# REV_2025.net
KiCad netlist of a schematic drawn in Altium Designer
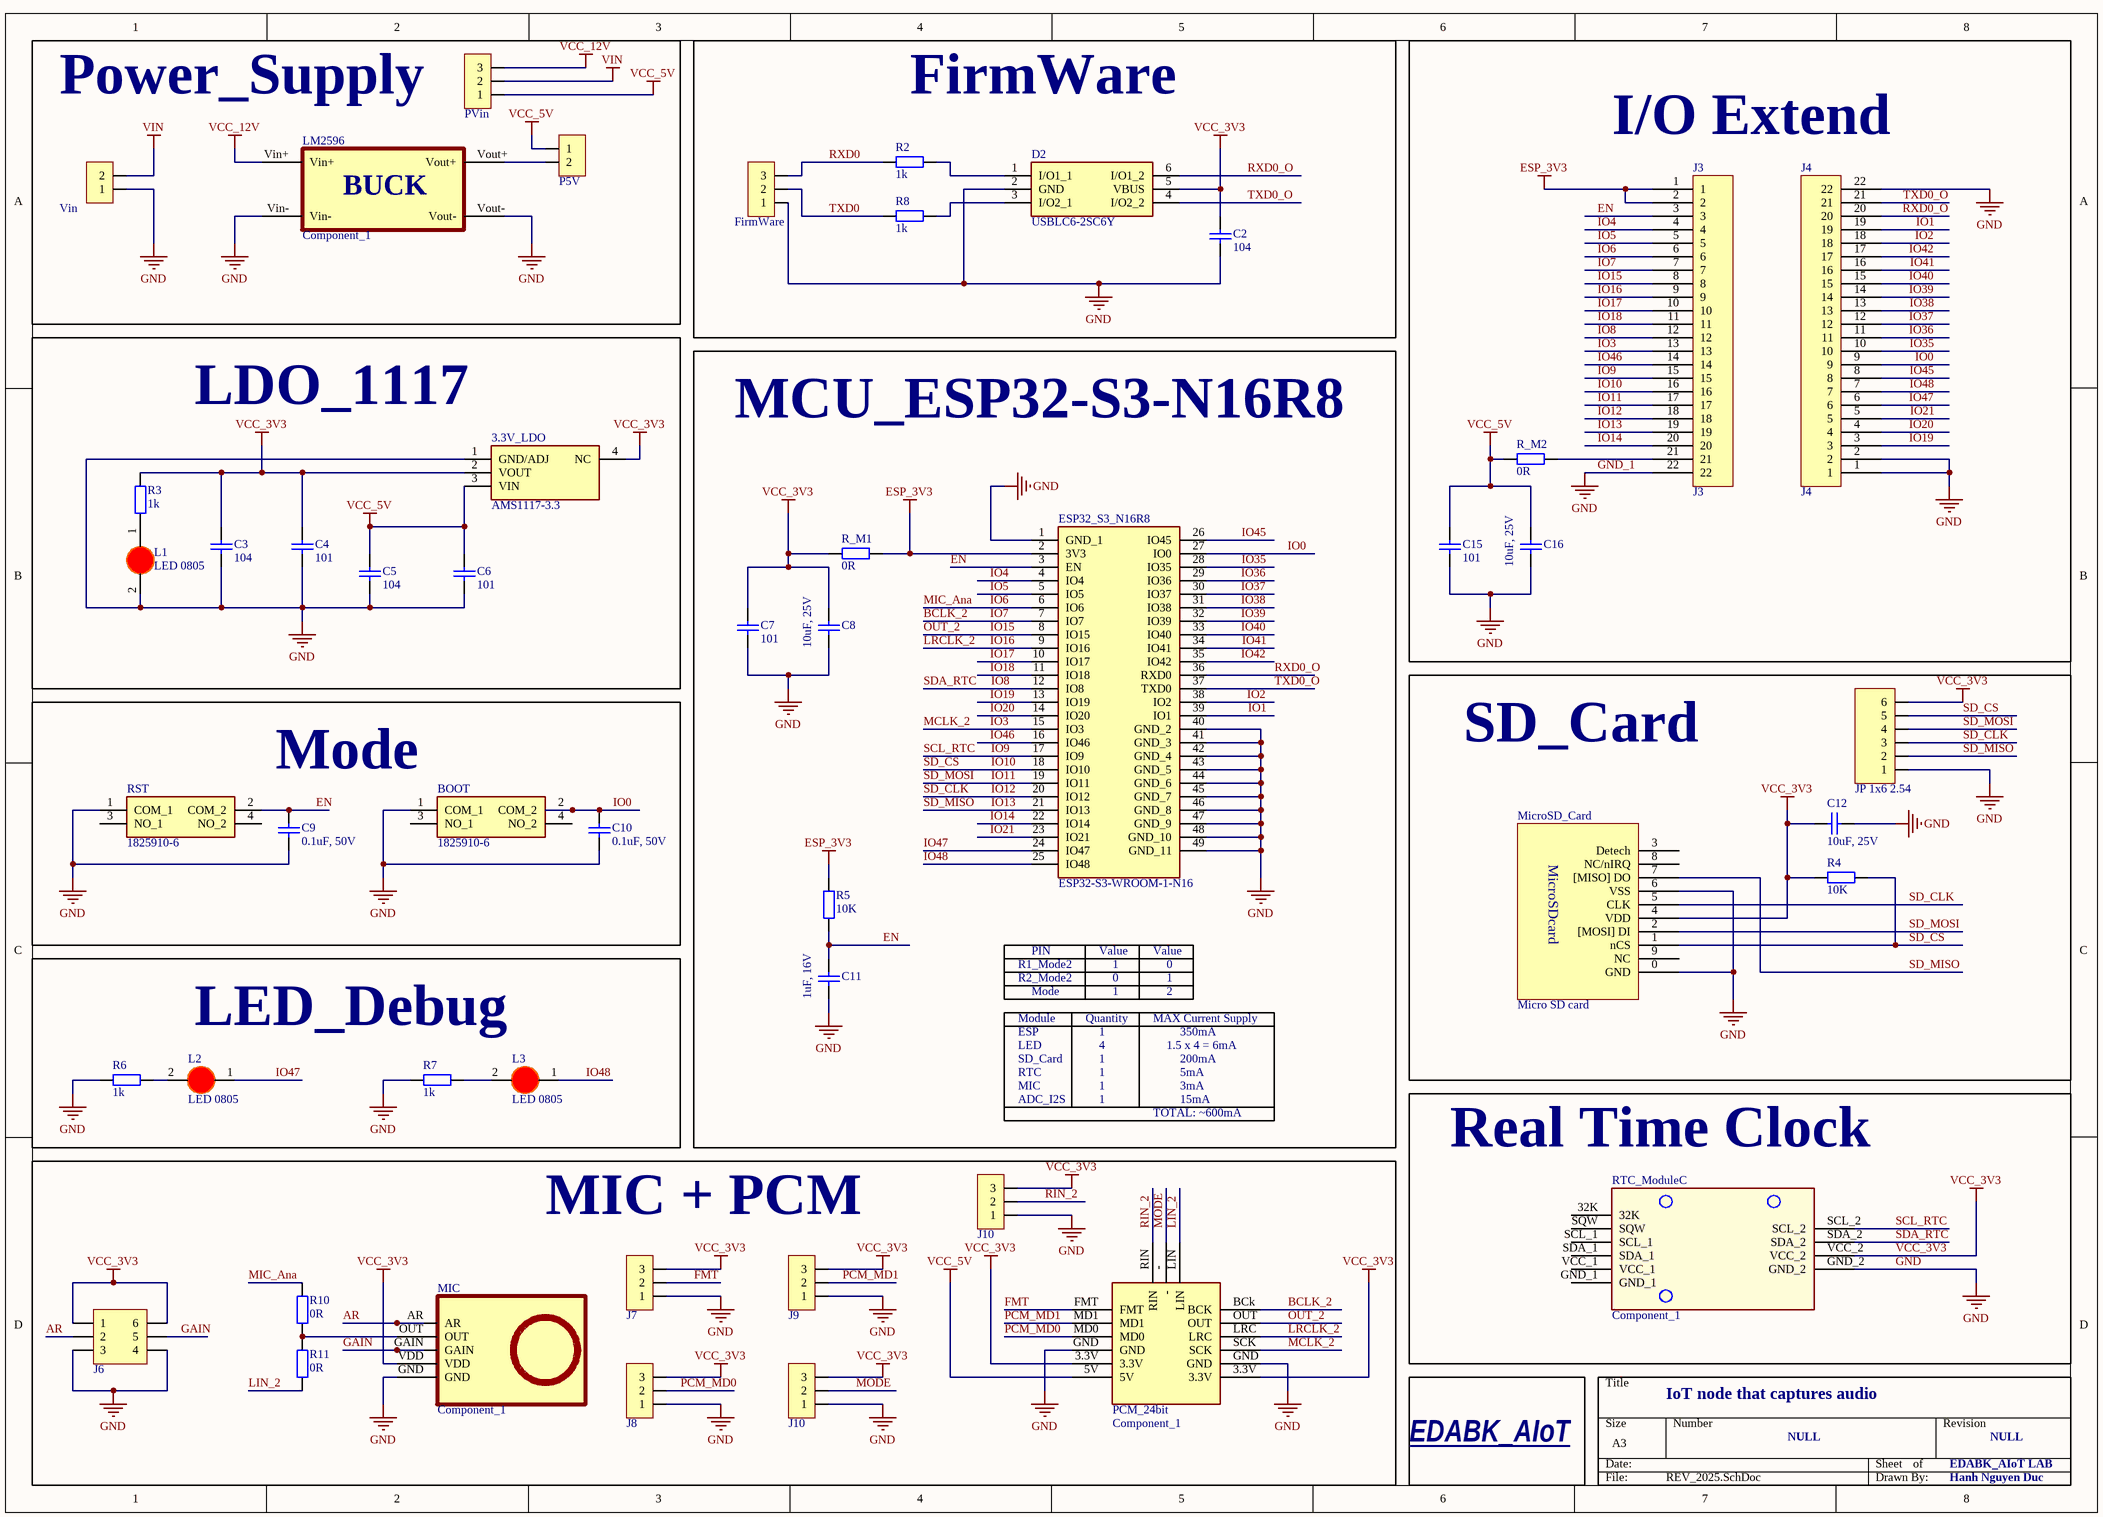
[diagram p0: REV_2025.SchDoc]

(export (version "E")
  (design (tool "Eeschema 10.0.6"))
  (components
    (comp (ref "3.3V_LDO")
      (value "AMS1117-3.3")
      (footprint "SamacSys:SOT229P700X180-4N")
      (description "Integrated Circuit")
      (libsource (lib "*") (part "AMS1117-3.3"))
    )
    (comp (ref "BOOT")
      (value "1825910-6")
      (footprint "SamacSys:18259106")
      (description "Switch")
      (fields (field (name "MOUSER PART NUMBER") "650-1825910-6"))
      (libsource (lib "*") (part "1825910-6"))
    )
    (comp (ref "C2")
      (value "104")
      (footprint "tu 0603")
      (description "Dán")
      (libsource (lib "Altium_Lib_by_KhueNguyenCreator") (part "Tu 0603 104 50V 10%"))
    )
    (comp (ref "C3")
      (value "104")
      (footprint "tu 0603")
      (description "Dán")
      (libsource (lib "Altium_Lib_by_KhueNguyenCreator") (part "Tu 0603 104 50V 10%"))
    )
    (comp (ref "C4")
      (value "101")
      (footprint "tu 0805")
      (description "Dán")
      (libsource (lib "Altium_Lib_by_KhueNguyenCreator") (part "Tu 0805 101 50V 20%"))
    )
    (comp (ref "C5")
      (value "104")
      (footprint "tu 0603")
      (description "Dán")
      (libsource (lib "Altium_Lib_by_KhueNguyenCreator") (part "Tu 0603 104 50V 10%"))
    )
    (comp (ref "C6")
      (value "101")
      (footprint "tu 0805")
      (description "Dán")
      (libsource (lib "Altium_Lib_by_KhueNguyenCreator") (part "Tu 0805 101 50V 20%"))
    )
    (comp (ref "C7")
      (value "101")
      (footprint "tu 0805")
      (description "Dán")
      (libsource (lib "Altium_Lib_by_KhueNguyenCreator") (part "Tu 0805 101 50V 20%"))
    )
    (comp (ref "C8")
      (value "10uF, 25V")
      (footprint "tu 0603")
      (description "Dán")
      (libsource (lib "Altium_Lib_by_KhueNguyenCreator") (part "Tu 0603 104 50V 10%"))
    )
    (comp (ref "C9")
      (value "0.1uF, 50V")
      (footprint "tu 0603")
      (description "Dán")
      (libsource (lib "Altium_Lib_by_KhueNguyenCreator") (part "Tu 0603 103 50V 10%"))
    )
    (comp (ref "C10")
      (value "0.1uF, 50V")
      (footprint "tu 0603")
      (description "Dán")
      (libsource (lib "Altium_Lib_by_KhueNguyenCreator") (part "Tu 0603 103 50V 10%"))
    )
    (comp (ref "C11")
      (value "1uF, 16V")
      (footprint "tu 0603")
      (description "Dán")
      (libsource (lib "Altium_Lib_by_KhueNguyenCreator") (part "Tu 0603 104 50V 10%"))
    )
    (comp (ref "C12")
      (value "10uF, 25V")
      (footprint "tu 0603")
      (description "Dán")
      (libsource (lib "Altium_Lib_by_KhueNguyenCreator") (part "Tu 0603 104 50V 10%"))
    )
    (comp (ref "C15")
      (value "101")
      (footprint "tu 0805")
      (description "Dán")
      (libsource (lib "Altium_Lib_by_KhueNguyenCreator") (part "Tu 0805 101 50V 20%"))
    )
    (comp (ref "C16")
      (value "10uF, 25V")
      (footprint "tu 0603")
      (description "Dán")
      (libsource (lib "Altium_Lib_by_KhueNguyenCreator") (part "Tu 0603 104 50V 10%"))
    )
    (comp (ref "D2")
      (value "USBLC6-2SC6Y")
      (footprint "SamacSys:SOT95P280X145-6N")
      (description "Diode")
      (fields (field (name "MOUSER PART NUMBER") "511-USBLC6-2SC6Y"))
      (libsource (lib "*") (part "USBLC6-2SC6Y"))
    )
    (comp (ref "ESP32_S3_N16R8")
      (value "ESP32-S3-WROOM-1-N16")
      (footprint "SamacSys:ESP32S3WROOM1N16")
      (description "Integrated Circuit")
      (fields (field (name "MOUSER PART NUMBER") "356-ESP32S3WROOM1N16"))
      (libsource (lib "*") (part "ESP32-S3-WROOM-1-N16"))
    )
    (comp (ref "FirmWare")
      (value "FirmWare")
      (footprint "JP 1x3 DC")
      (description "Cắm")
      (libsource (lib "Altium_Lib_by_KhueNguyenCreator") (part "JP 1x3 2.54 Duc Cong"))
    )
    (comp (ref "FMT")
      (value "J7")
      (footprint "JP 1x3 DT")
      (description "Cắm")
      (libsource (lib "Altium_Lib_by_KhueNguyenCreator") (part "JP 1x3 2.54 Duc Thang"))
    )
    (comp (ref "J3")
      (value "J3")
      (footprint "Jump22pins:PCBComponent_1")
      (libsource (lib "Jump22pins") (part "Component_1"))
    )
    (comp (ref "J4")
      (value "J4")
      (footprint "Jump22pins:PCBComponent_1")
      (libsource (lib "") (part "Component_1_1"))
    )
    (comp (ref "JP3")
      (value "JP 1x6 2.54")
      (footprint "JP 1x6 DT")
      (description "Cắm")
      (libsource (lib "Altium_Lib_by_KhueNguyenCreator") (part "JP 1x6 2.54 Duc Thang"))
    )
    (comp (ref "L1")
      (value "LED 0805")
      (footprint "LED-0805-Red")
      (description "Dán")
      (libsource (lib "Altium_Lib_by_KhueNguyenCreator") (part "LED 0805 Do"))
    )
    (comp (ref "L2")
      (value "LED 0805")
      (footprint "LED-0805-Red")
      (description "Dán")
      (libsource (lib "Altium_Lib_by_KhueNguyenCreator") (part "LED 0805 Do"))
    )
    (comp (ref "L3")
      (value "LED 0805")
      (footprint "LED-0805-Red")
      (description "Dán")
      (libsource (lib "Altium_Lib_by_KhueNguyenCreator") (part "LED 0805 Do"))
    )
    (comp (ref "LM2596")
      (value "Component_1")
      (footprint "LM2596_MODULE:PCBComponent_1")
      (libsource (lib "LM2596_MODULE") (part "Component_1"))
    )
    (comp (ref "MD0")
      (value "J8")
      (footprint "JP 1x3 DT")
      (description "Cắm")
      (libsource (lib "Altium_Lib_by_KhueNguyenCreator") (part "JP 1x3 2.54 Duc Thang"))
    )
    (comp (ref "MD1")
      (value "J9")
      (footprint "JP 1x3 DT")
      (description "Cắm")
      (libsource (lib "Altium_Lib_by_KhueNguyenCreator") (part "JP 1x3 2.54 Duc Thang"))
    )
    (comp (ref "MIC")
      (value "Component_1")
      (footprint "MAX_9814_Module:PCBComponent_1")
      (libsource (lib "MAX_9814_Module") (part "Component_1"))
    )
    (comp (ref "MicroSD_Card")
      (value "Micro SD card")
      (footprint "MicroSD")
      (libsource (lib "Altium_Lib_by_KhueNguyenCreator") (part "Micro SD card"))
    )
    (comp (ref "MIC_Mode")
      (value "J6")
      (footprint "JP 2x3 DT")
      (description "Cắm")
      (libsource (lib "Altium_Lib_by_KhueNguyenCreator") (part "JP 2x3 2.54 Duc Thang"))
    )
    (comp (ref "P5V")
      (value "P5V")
      (footprint "JP 1x2 DT")
      (description "Cắm")
      (libsource (lib "Altium_Lib_by_KhueNguyenCreator") (part "JP 1x2 2.54 Duc Thang"))
    )
    (comp (ref "PCM_24bit")
      (value "Component_1")
      (footprint "PCM1808:PCBComponent_1")
      (libsource (lib "PCM1808") (part "Component_1"))
    )
    (comp (ref "PVin")
      (value "PVin")
      (footprint "JP 1x3 DT")
      (description "Cắm")
      (libsource (lib "Altium_Lib_by_KhueNguyenCreator") (part "JP 1x3 2.54 Duc Thang"))
    )
    (comp (ref "R-L")
      (value "J10")
      (footprint "JP 1x3 DT")
      (description "Cắm")
      (libsource (lib "Altium_Lib_by_KhueNguyenCreator") (part "JP 1x3 2.54 Duc Thang"))
    )
    (comp (ref "R2")
      (value "1k")
      (footprint "tro smd 0805")
      (description "Dán")
      (libsource (lib "Altium_Lib_by_KhueNguyenCreator") (part "Tro 0805 1% 1k"))
    )
    (comp (ref "R3")
      (value "1k")
      (footprint "tro smd 0805")
      (description "Dán")
      (libsource (lib "Altium_Lib_by_KhueNguyenCreator") (part "Tro 0805 1% 1k"))
    )
    (comp (ref "R4")
      (value "10K")
      (footprint "tro smd 0805")
      (description "Dán")
      (libsource (lib "Altium_Lib_by_KhueNguyenCreator") (part "Tro 0805 1% 1k"))
    )
    (comp (ref "R5")
      (value "10K")
      (footprint "tro smd 0805")
      (description "Dán")
      (libsource (lib "Altium_Lib_by_KhueNguyenCreator") (part "Tro 0805 1% 1k"))
    )
    (comp (ref "R6")
      (value "1k")
      (footprint "tro smd 0805")
      (description "Dán")
      (libsource (lib "Altium_Lib_by_KhueNguyenCreator") (part "Tro 0805 1% 1k"))
    )
    (comp (ref "R7")
      (value "1k")
      (footprint "tro smd 0805")
      (description "Dán")
      (libsource (lib "Altium_Lib_by_KhueNguyenCreator") (part "Tro 0805 1% 1k"))
    )
    (comp (ref "R8")
      (value "1k")
      (footprint "tro smd 0805")
      (description "Dán")
      (libsource (lib "Altium_Lib_by_KhueNguyenCreator") (part "Tro 0805 1% 1k"))
    )
    (comp (ref "R10")
      (value "0R")
      (footprint "tro smd 0603")
      (description "Dán")
      (libsource (lib "Altium_Lib_by_KhueNguyenCreator") (part "Tro 0603 1% 0R"))
    )
    (comp (ref "R11")
      (value "0R")
      (footprint "tro smd 0603")
      (description "Dán")
      (libsource (lib "Altium_Lib_by_KhueNguyenCreator") (part "Tro 0603 1% 0R"))
    )
    (comp (ref "RIN")
      (value "J10")
      (footprint "JP 1x3 DT")
      (description "Cắm")
      (libsource (lib "Altium_Lib_by_KhueNguyenCreator") (part "JP 1x3 2.54 Duc Thang"))
    )
    (comp (ref "RST")
      (value "1825910-6")
      (footprint "SamacSys:18259106")
      (description "Switch")
      (fields (field (name "MOUSER PART NUMBER") "650-1825910-6"))
      (libsource (lib "*") (part "1825910-6"))
    )
    (comp (ref "RTC_Module")
      (value "Component_1")
      (footprint "RTS_Module_DS3231:PCBComponent_1")
      (libsource (lib "RTC_Module_DS3231") (part "Component_1"))
    )
    (comp (ref "R_M1")
      (value "0R")
      (footprint "tro smd 0603")
      (description "Dán")
      (libsource (lib "Altium_Lib_by_KhueNguyenCreator") (part "Tro 0603 1% 0R"))
    )
    (comp (ref "R_M2")
      (value "0R")
      (footprint "tro smd 0603")
      (description "Dán")
      (libsource (lib "Altium_Lib_by_KhueNguyenCreator") (part "Tro 0603 1% 0R"))
    )
    (comp (ref "Vin")
      (value "Vin")
      (footprint "JP 1x2 DC")
      (description "Cắm")
      (libsource (lib "Altium_Lib_by_KhueNguyenCreator") (part "JP 1x2 2.54 Duc Cong"))
    )
  )
  (nets
    (net (code "1") (name "/AR") (class "Default")
      (node (ref "MIC") (pin "AR") (pinfunction "AR_AR") (pintype "passive"))
      (node (ref "MIC_Mode") (pin "2") (pinfunction "2_2") (pintype "passive"))
    )
    (net (code "2") (name "/BCLK_2") (class "Default")
      (node (ref "ESP32_S3_N16R8") (pin "7") (pinfunction "IO7_7") (pintype "passive"))
      (node (ref "J3") (pin "7") (pinfunction "7_7") (pintype "passive"))
      (node (ref "PCM_24bit") (pin "BCk") (pinfunction "BCK_BCk") (pintype "passive"))
    )
    (net (code "3") (name "/EN") (class "Default")
      (node (ref "C11") (pin "1") (pinfunction "1_1") (pintype "passive"))
      (node (ref "C9") (pin "1") (pinfunction "1_1") (pintype "passive"))
      (node (ref "ESP32_S3_N16R8") (pin "3") (pinfunction "EN_3") (pintype "passive"))
      (node (ref "J3") (pin "3") (pinfunction "3_3") (pintype "passive"))
      (node (ref "R5") (pin "2") (pinfunction "2_2") (pintype "passive"))
      (node (ref "RST") (pin "2") (pinfunction "COM_2_2") (pintype "passive"))
    )
    (net (code "4") (name "/FMT") (class "Default")
      (node (ref "FMT") (pin "2") (pinfunction "2_2") (pintype "passive"))
      (node (ref "PCM_24bit") (pin "FMT") (pinfunction "FMT_FMT") (pintype "passive"))
    )
    (net (code "5") (name "/GAIN") (class "Default")
      (node (ref "MIC") (pin "GAIN") (pinfunction "GAIN_GAIN") (pintype "passive"))
      (node (ref "MIC_Mode") (pin "5") (pinfunction "5_5") (pintype "passive"))
    )
    (net (code "6") (name "/IO0") (class "Default")
      (node (ref "BOOT") (pin "2") (pinfunction "COM_2_2") (pintype "passive"))
      (node (ref "C10") (pin "1") (pinfunction "1_1") (pintype "passive"))
      (node (ref "ESP32_S3_N16R8") (pin "27") (pinfunction "IO0_27") (pintype "passive"))
      (node (ref "J4") (pin "9") (pinfunction "9_9") (pintype "passive"))
    )
    (net (code "7") (name "/IO1") (class "Default")
      (node (ref "ESP32_S3_N16R8") (pin "39") (pinfunction "IO1_39") (pintype "passive"))
      (node (ref "J4") (pin "19") (pinfunction "19_19") (pintype "passive"))
    )
    (net (code "8") (name "/IO2") (class "Default")
      (node (ref "ESP32_S3_N16R8") (pin "38") (pinfunction "IO2_38") (pintype "passive"))
      (node (ref "J4") (pin "18") (pinfunction "18_18") (pintype "passive"))
    )
    (net (code "9") (name "/IO3") (class "Default")
      (node (ref "ESP32_S3_N16R8") (pin "15") (pinfunction "IO3_15") (pintype "passive"))
      (node (ref "J3") (pin "13") (pinfunction "13_13") (pintype "passive"))
      (node (ref "PCM_24bit") (pin "SCK") (pinfunction "SCK_SCK") (pintype "passive"))
    )
    (net (code "10") (name "/IO4") (class "Default")
      (node (ref "ESP32_S3_N16R8") (pin "4") (pinfunction "IO4_4") (pintype "passive"))
      (node (ref "J3") (pin "4") (pinfunction "4_4") (pintype "passive"))
    )
    (net (code "11") (name "/IO5") (class "Default")
      (node (ref "ESP32_S3_N16R8") (pin "5") (pinfunction "IO5_5") (pintype "passive"))
      (node (ref "J3") (pin "5") (pinfunction "5_5") (pintype "passive"))
    )
    (net (code "12") (name "/IO6") (class "Default")
      (node (ref "ESP32_S3_N16R8") (pin "6") (pinfunction "IO6_6") (pintype "passive"))
      (node (ref "J3") (pin "6") (pinfunction "6_6") (pintype "passive"))
      (node (ref "R10") (pin "2") (pinfunction "2_2") (pintype "passive"))
    )
    (net (code "13") (name "/IO8") (class "Default")
      (node (ref "ESP32_S3_N16R8") (pin "12") (pinfunction "IO8_12") (pintype "passive"))
      (node (ref "J3") (pin "12") (pinfunction "12_12") (pintype "passive"))
      (node (ref "RTC_Module") (pin "SDA_2") (pinfunction "SDA_2_SDA_2") (pintype "passive"))
    )
    (net (code "14") (name "/IO9") (class "Default")
      (node (ref "ESP32_S3_N16R8") (pin "17") (pinfunction "IO9_17") (pintype "passive"))
      (node (ref "J3") (pin "15") (pinfunction "15_15") (pintype "passive"))
      (node (ref "RTC_Module") (pin "SCL_2") (pinfunction "SCL_2_SCL_2") (pintype "passive"))
    )
    (net (code "15") (name "/IO10") (class "Default")
      (node (ref "ESP32_S3_N16R8") (pin "18") (pinfunction "IO10_18") (pintype "passive"))
      (node (ref "J3") (pin "16") (pinfunction "16_16") (pintype "passive"))
      (node (ref "JP3") (pin "5") (pinfunction "5_5") (pintype "passive"))
      (node (ref "MicroSD_Card") (pin "1") (pinfunction "nCS_1") (pintype "passive"))
      (node (ref "R4") (pin "2") (pinfunction "2_2") (pintype "passive"))
    )
    (net (code "16") (name "/IO11") (class "Default")
      (node (ref "ESP32_S3_N16R8") (pin "19") (pinfunction "IO11_19") (pintype "passive"))
      (node (ref "J3") (pin "17") (pinfunction "17_17") (pintype "passive"))
      (node (ref "JP3") (pin "4") (pinfunction "4_4") (pintype "passive"))
      (node (ref "MicroSD_Card") (pin "2") (pinfunction "[MOSI]_DI_2") (pintype "passive"))
    )
    (net (code "17") (name "/IO12") (class "Default")
      (node (ref "ESP32_S3_N16R8") (pin "20") (pinfunction "IO12_20") (pintype "passive"))
      (node (ref "J3") (pin "18") (pinfunction "18_18") (pintype "passive"))
      (node (ref "JP3") (pin "3") (pinfunction "3_3") (pintype "passive"))
      (node (ref "MicroSD_Card") (pin "5") (pinfunction "CLK_5") (pintype "passive"))
    )
    (net (code "18") (name "/IO13") (class "Default")
      (node (ref "ESP32_S3_N16R8") (pin "21") (pinfunction "IO13_21") (pintype "passive"))
      (node (ref "J3") (pin "19") (pinfunction "19_19") (pintype "passive"))
      (node (ref "JP3") (pin "2") (pinfunction "2_2") (pintype "passive"))
      (node (ref "MicroSD_Card") (pin "7") (pinfunction "[MISO]_DO_7") (pintype "passive"))
    )
    (net (code "19") (name "/IO14") (class "Default")
      (node (ref "ESP32_S3_N16R8") (pin "22") (pinfunction "IO14_22") (pintype "passive"))
      (node (ref "J3") (pin "20") (pinfunction "20_20") (pintype "passive"))
    )
    (net (code "20") (name "/IO15") (class "Default")
      (node (ref "ESP32_S3_N16R8") (pin "8") (pinfunction "IO15_8") (pintype "passive"))
      (node (ref "J3") (pin "8") (pinfunction "8_8") (pintype "passive"))
      (node (ref "PCM_24bit") (pin "OUT") (pinfunction "OUT_OUT") (pintype "passive"))
    )
    (net (code "21") (name "/IO16") (class "Default")
      (node (ref "ESP32_S3_N16R8") (pin "9") (pinfunction "IO16_9") (pintype "passive"))
      (node (ref "J3") (pin "9") (pinfunction "9_9") (pintype "passive"))
      (node (ref "PCM_24bit") (pin "LRC") (pinfunction "LRC_LRC") (pintype "passive"))
    )
    (net (code "22") (name "/IO17") (class "Default")
      (node (ref "ESP32_S3_N16R8") (pin "10") (pinfunction "IO17_10") (pintype "passive"))
      (node (ref "J3") (pin "10") (pinfunction "10_10") (pintype "passive"))
    )
    (net (code "23") (name "/IO18") (class "Default")
      (node (ref "ESP32_S3_N16R8") (pin "11") (pinfunction "IO18_11") (pintype "passive"))
      (node (ref "J3") (pin "11") (pinfunction "11_11") (pintype "passive"))
    )
    (net (code "24") (name "/IO19") (class "Default")
      (node (ref "ESP32_S3_N16R8") (pin "13") (pinfunction "IO19_13") (pintype "passive"))
      (node (ref "J4") (pin "3") (pinfunction "3_3") (pintype "passive"))
    )
    (net (code "25") (name "/IO20") (class "Default")
      (node (ref "ESP32_S3_N16R8") (pin "14") (pinfunction "IO20_14") (pintype "passive"))
      (node (ref "J4") (pin "4") (pinfunction "4_4") (pintype "passive"))
    )
    (net (code "26") (name "/IO21") (class "Default")
      (node (ref "ESP32_S3_N16R8") (pin "23") (pinfunction "IO21_23") (pintype "passive"))
      (node (ref "J4") (pin "5") (pinfunction "5_5") (pintype "passive"))
    )
    (net (code "27") (name "/IO35") (class "Default")
      (node (ref "ESP32_S3_N16R8") (pin "28") (pinfunction "IO35_28") (pintype "passive"))
      (node (ref "J4") (pin "10") (pinfunction "10_10") (pintype "passive"))
    )
    (net (code "28") (name "/IO36") (class "Default")
      (node (ref "ESP32_S3_N16R8") (pin "29") (pinfunction "IO36_29") (pintype "passive"))
      (node (ref "J4") (pin "11") (pinfunction "11_11") (pintype "passive"))
    )
    (net (code "29") (name "/IO37") (class "Default")
      (node (ref "ESP32_S3_N16R8") (pin "30") (pinfunction "IO37_30") (pintype "passive"))
      (node (ref "J4") (pin "12") (pinfunction "12_12") (pintype "passive"))
    )
    (net (code "30") (name "/IO38") (class "Default")
      (node (ref "ESP32_S3_N16R8") (pin "31") (pinfunction "IO38_31") (pintype "passive"))
      (node (ref "J4") (pin "13") (pinfunction "13_13") (pintype "passive"))
    )
    (net (code "31") (name "/IO39") (class "Default")
      (node (ref "ESP32_S3_N16R8") (pin "32") (pinfunction "IO39_32") (pintype "passive"))
      (node (ref "J4") (pin "14") (pinfunction "14_14") (pintype "passive"))
    )
    (net (code "32") (name "/IO40") (class "Default")
      (node (ref "ESP32_S3_N16R8") (pin "33") (pinfunction "IO40_33") (pintype "passive"))
      (node (ref "J4") (pin "15") (pinfunction "15_15") (pintype "passive"))
    )
    (net (code "33") (name "/IO41") (class "Default")
      (node (ref "ESP32_S3_N16R8") (pin "34") (pinfunction "IO41_34") (pintype "passive"))
      (node (ref "J4") (pin "16") (pinfunction "16_16") (pintype "passive"))
    )
    (net (code "34") (name "/IO42") (class "Default")
      (node (ref "ESP32_S3_N16R8") (pin "35") (pinfunction "IO42_35") (pintype "passive"))
      (node (ref "J4") (pin "17") (pinfunction "17_17") (pintype "passive"))
    )
    (net (code "35") (name "/IO45") (class "Default")
      (node (ref "ESP32_S3_N16R8") (pin "26") (pinfunction "IO45_26") (pintype "passive"))
      (node (ref "J4") (pin "8") (pinfunction "8_8") (pintype "passive"))
    )
    (net (code "36") (name "/IO46") (class "Default")
      (node (ref "ESP32_S3_N16R8") (pin "16") (pinfunction "IO46_16") (pintype "passive"))
      (node (ref "J3") (pin "14") (pinfunction "14_14") (pintype "passive"))
    )
    (net (code "37") (name "/IO47") (class "Default")
      (node (ref "ESP32_S3_N16R8") (pin "24") (pinfunction "IO47_24") (pintype "passive"))
      (node (ref "J4") (pin "6") (pinfunction "6_6") (pintype "passive"))
      (node (ref "L2") (pin "1") (pinfunction "A_1") (pintype "passive"))
    )
    (net (code "38") (name "/IO48") (class "Default")
      (node (ref "ESP32_S3_N16R8") (pin "25") (pinfunction "IO48_25") (pintype "passive"))
      (node (ref "J4") (pin "7") (pinfunction "7_7") (pintype "passive"))
      (node (ref "L3") (pin "1") (pinfunction "A_1") (pintype "passive"))
    )
    (net (code "39") (name "/LIN_2") (class "Default")
      (node (ref "PCM_24bit") (pin "LIN") (pinfunction "LIN_LIN") (pintype "passive"))
      (node (ref "R11") (pin "1") (pinfunction "1_1") (pintype "passive"))
    )
    (net (code "40") (name "/MODE") (class "Default")
      (node (ref "PCM_24bit") (pin "-") (pinfunction "-_-") (pintype "passive"))
      (node (ref "R-L") (pin "2") (pinfunction "2_2") (pintype "passive"))
    )
    (net (code "41") (name "/PCM_MD0") (class "Default")
      (node (ref "MD0") (pin "2") (pinfunction "2_2") (pintype "passive"))
      (node (ref "PCM_24bit") (pin "MD0") (pinfunction "MD0_MD0") (pintype "passive"))
    )
    (net (code "42") (name "/PCM_MD1") (class "Default")
      (node (ref "MD1") (pin "2") (pinfunction "2_2") (pintype "passive"))
      (node (ref "PCM_24bit") (pin "MD1") (pinfunction "MD1_MD1") (pintype "passive"))
    )
    (net (code "43") (name "/RIN_2") (class "Default")
      (node (ref "PCM_24bit") (pin "RIN") (pinfunction "RIN_RIN") (pintype "passive"))
      (node (ref "RIN") (pin "2") (pinfunction "2_2") (pintype "passive"))
    )
    (net (code "44") (name "/RXD0") (class "Default")
      (node (ref "FirmWare") (pin "3") (pinfunction "3_3") (pintype "passive"))
      (node (ref "R2") (pin "2") (pinfunction "2_2") (pintype "passive"))
    )
    (net (code "45") (name "/RXD0_O") (class "Default")
      (node (ref "D2") (pin "6") (pinfunction "I/O1_2_6") (pintype "passive"))
      (node (ref "ESP32_S3_N16R8") (pin "36") (pinfunction "RXD0_36") (pintype "passive"))
      (node (ref "J4") (pin "20") (pinfunction "20_20") (pintype "passive"))
    )
    (net (code "46") (name "/TXD0") (class "Default")
      (node (ref "FirmWare") (pin "2") (pinfunction "2_2") (pintype "passive"))
      (node (ref "R8") (pin "2") (pinfunction "2_2") (pintype "passive"))
    )
    (net (code "47") (name "/TXD0_O") (class "Default")
      (node (ref "D2") (pin "4") (pinfunction "I/O2_2_4") (pintype "passive"))
      (node (ref "ESP32_S3_N16R8") (pin "37") (pinfunction "TXD0_37") (pintype "passive"))
      (node (ref "J4") (pin "21") (pinfunction "21_21") (pintype "passive"))
    )
    (net (code "48") (name "ESP_3V3") (class "Default")
      (node (ref "ESP32_S3_N16R8") (pin "2") (pinfunction "3V3_2") (pintype "passive"))
      (node (ref "J3") (pin "1") (pinfunction "1_1") (pintype "passive"))
      (node (ref "J3") (pin "2") (pinfunction "2_2") (pintype "passive"))
      (node (ref "R5") (pin "1") (pinfunction "1_1") (pintype "passive"))
      (node (ref "R_M1") (pin "1") (pinfunction "1_1") (pintype "passive"))
    )
    (net (code "49") (name "GND") (class "Default")
      (node (ref "3.3V_LDO") (pin "1") (pinfunction "GND/ADJ_1") (pintype "passive"))
      (node (ref "BOOT") (pin "1") (pinfunction "COM_1_1") (pintype "passive"))
      (node (ref "C10") (pin "2") (pinfunction "2_2") (pintype "passive"))
      (node (ref "C11") (pin "2") (pinfunction "2_2") (pintype "passive"))
      (node (ref "C12") (pin "2") (pinfunction "2_2") (pintype "passive"))
      (node (ref "C15") (pin "2") (pinfunction "2_2") (pintype "passive"))
      (node (ref "C16") (pin "2") (pinfunction "2_2") (pintype "passive"))
      (node (ref "C2") (pin "2") (pinfunction "2_2") (pintype "passive"))
      (node (ref "C3") (pin "2") (pinfunction "2_2") (pintype "passive"))
      (node (ref "C4") (pin "2") (pinfunction "2_2") (pintype "passive"))
      (node (ref "C5") (pin "2") (pinfunction "2_2") (pintype "passive"))
      (node (ref "C6") (pin "2") (pinfunction "2_2") (pintype "passive"))
      (node (ref "C7") (pin "2") (pinfunction "2_2") (pintype "passive"))
      (node (ref "C8") (pin "2") (pinfunction "2_2") (pintype "passive"))
      (node (ref "C9") (pin "2") (pinfunction "2_2") (pintype "passive"))
      (node (ref "D2") (pin "2") (pinfunction "GND_2") (pintype "passive"))
      (node (ref "ESP32_S3_N16R8") (pin "1") (pinfunction "GND_1_1") (pintype "passive"))
      (node (ref "ESP32_S3_N16R8") (pin "40") (pinfunction "GND_2_40") (pintype "passive"))
      (node (ref "ESP32_S3_N16R8") (pin "41") (pinfunction "GND_3_41") (pintype "passive"))
      (node (ref "ESP32_S3_N16R8") (pin "42") (pinfunction "GND_4_42") (pintype "passive"))
      (node (ref "ESP32_S3_N16R8") (pin "43") (pinfunction "GND_5_43") (pintype "passive"))
      (node (ref "ESP32_S3_N16R8") (pin "44") (pinfunction "GND_6_44") (pintype "passive"))
      (node (ref "ESP32_S3_N16R8") (pin "45") (pinfunction "GND_7_45") (pintype "passive"))
      (node (ref "ESP32_S3_N16R8") (pin "46") (pinfunction "GND_8_46") (pintype "passive"))
      (node (ref "ESP32_S3_N16R8") (pin "47") (pinfunction "GND_9_47") (pintype "passive"))
      (node (ref "ESP32_S3_N16R8") (pin "48") (pinfunction "GND_10_48") (pintype "passive"))
      (node (ref "ESP32_S3_N16R8") (pin "49") (pinfunction "GND_11_49") (pintype "passive"))
      (node (ref "FMT") (pin "1") (pinfunction "1_1") (pintype "passive"))
      (node (ref "FirmWare") (pin "1") (pinfunction "1_1") (pintype "passive"))
      (node (ref "J3") (pin "22") (pinfunction "22_22") (pintype "passive"))
      (node (ref "J4") (pin "1") (pinfunction "1_1") (pintype "passive"))
      (node (ref "J4") (pin "2") (pinfunction "2_2") (pintype "passive"))
      (node (ref "J4") (pin "22") (pinfunction "22_22") (pintype "passive"))
      (node (ref "JP3") (pin "1") (pinfunction "1_1") (pintype "passive"))
      (node (ref "L1") (pin "2") (pinfunction "K_2") (pintype "passive"))
      (node (ref "LM2596") (pin "Vin-") (pinfunction "Vin-_Vin-") (pintype "passive"))
      (node (ref "LM2596") (pin "Vout-") (pinfunction "Vout-_Vout-") (pintype "passive"))
      (node (ref "MD0") (pin "1") (pinfunction "1_1") (pintype "passive"))
      (node (ref "MD1") (pin "1") (pinfunction "1_1") (pintype "passive"))
      (node (ref "MIC") (pin "GND") (pinfunction "GND_GND") (pintype "passive"))
      (node (ref "MIC_Mode") (pin "3") (pinfunction "3_3") (pintype "passive"))
      (node (ref "MIC_Mode") (pin "4") (pinfunction "4_4") (pintype "passive"))
      (node (ref "MicroSD_Card") (pin "0") (pinfunction "GND_0") (pintype "passive"))
      (node (ref "MicroSD_Card") (pin "6") (pinfunction "VSS_6") (pintype "passive"))
      (node (ref "PCM_24bit") (pin "GND") (pinfunction "GND_GND") (pintype "passive"))
      (node (ref "R-L") (pin "1") (pinfunction "1_1") (pintype "passive"))
      (node (ref "R6") (pin "2") (pinfunction "2_2") (pintype "passive"))
      (node (ref "R7") (pin "2") (pinfunction "2_2") (pintype "passive"))
      (node (ref "RIN") (pin "1") (pinfunction "1_1") (pintype "passive"))
      (node (ref "RST") (pin "1") (pinfunction "COM_1_1") (pintype "passive"))
      (node (ref "RTC_Module") (pin "GND_2") (pinfunction "GND_2_GND_2") (pintype "passive"))
      (node (ref "Vin") (pin "1") (pinfunction "1_1") (pintype "passive"))
    )
    (net (code "50") (name "Net-(D2-I{slash}O1_1)") (class "Default")
      (node (ref "D2") (pin "1") (pinfunction "I/O1_1_1") (pintype "passive"))
      (node (ref "R2") (pin "1") (pinfunction "1_1") (pintype "passive"))
    )
    (net (code "51") (name "Net-(D2-I{slash}O2_1)") (class "Default")
      (node (ref "D2") (pin "3") (pinfunction "I/O2_1_3") (pintype "passive"))
      (node (ref "R8") (pin "1") (pinfunction "1_1") (pintype "passive"))
    )
    (net (code "52") (name "Net-(J3-Pad21)") (class "Default")
      (node (ref "J3") (pin "21") (pinfunction "21_21") (pintype "passive"))
      (node (ref "R_M2") (pin "1") (pinfunction "1_1") (pintype "passive"))
    )
    (net (code "53") (name "Net-(L1-A)") (class "Default")
      (node (ref "L1") (pin "1") (pinfunction "A_1") (pintype "passive"))
      (node (ref "R3") (pin "1") (pinfunction "1_1") (pintype "passive"))
    )
    (net (code "54") (name "Net-(L2-K)") (class "Default")
      (node (ref "L2") (pin "2") (pinfunction "K_2") (pintype "passive"))
      (node (ref "R6") (pin "1") (pinfunction "1_1") (pintype "passive"))
    )
    (net (code "55") (name "Net-(L3-K)") (class "Default")
      (node (ref "L3") (pin "2") (pinfunction "K_2") (pintype "passive"))
      (node (ref "R7") (pin "1") (pinfunction "1_1") (pintype "passive"))
    )
    (net (code "56") (name "Net-(LM2596-PadVout+)") (class "Default")
      (node (ref "LM2596") (pin "Vout+") (pinfunction "Vout+_Vout+") (pintype "passive"))
      (node (ref "P5V") (pin "2") (pinfunction "2_2") (pintype "passive"))
    )
    (net (code "57") (name "Net-(MIC-PadOUT)") (class "Default")
      (node (ref "MIC") (pin "OUT") (pinfunction "OUT_OUT") (pintype "passive"))
      (node (ref "R10") (pin "1") (pinfunction "1_1") (pintype "passive"))
      (node (ref "R11") (pin "2") (pinfunction "2_2") (pintype "passive"))
    )
    (net (code "58") (name "VCC_3V3") (class "Default")
      (node (ref "3.3V_LDO") (pin "2") (pinfunction "VOUT_2") (pintype "passive"))
      (node (ref "3.3V_LDO") (pin "4") (pinfunction "NC_4") (pintype "passive"))
      (node (ref "C12") (pin "1") (pinfunction "1_1") (pintype "passive"))
      (node (ref "C2") (pin "1") (pinfunction "1_1") (pintype "passive"))
      (node (ref "C3") (pin "1") (pinfunction "1_1") (pintype "passive"))
      (node (ref "C4") (pin "1") (pinfunction "1_1") (pintype "passive"))
      (node (ref "C7") (pin "1") (pinfunction "1_1") (pintype "passive"))
      (node (ref "C8") (pin "1") (pinfunction "1_1") (pintype "passive"))
      (node (ref "D2") (pin "5") (pinfunction "VBUS_5") (pintype "passive"))
      (node (ref "FMT") (pin "3") (pinfunction "3_3") (pintype "passive"))
      (node (ref "JP3") (pin "6") (pinfunction "6_6") (pintype "passive"))
      (node (ref "MD0") (pin "3") (pinfunction "3_3") (pintype "passive"))
      (node (ref "MD1") (pin "3") (pinfunction "3_3") (pintype "passive"))
      (node (ref "MIC") (pin "VDD") (pinfunction "VDD_VDD") (pintype "passive"))
      (node (ref "MIC_Mode") (pin "1") (pinfunction "1_1") (pintype "passive"))
      (node (ref "MIC_Mode") (pin "6") (pinfunction "6_6") (pintype "passive"))
      (node (ref "MicroSD_Card") (pin "4") (pinfunction "VDD_4") (pintype "passive"))
      (node (ref "PCM_24bit") (pin "3.3V") (pinfunction "3.3V_3.3V") (pintype "passive"))
      (node (ref "R-L") (pin "3") (pinfunction "3_3") (pintype "passive"))
      (node (ref "R3") (pin "2") (pinfunction "2_2") (pintype "passive"))
      (node (ref "R4") (pin "1") (pinfunction "1_1") (pintype "passive"))
      (node (ref "RIN") (pin "3") (pinfunction "3_3") (pintype "passive"))
      (node (ref "RTC_Module") (pin "VCC_2") (pinfunction "VCC_2_VCC_2") (pintype "passive"))
      (node (ref "R_M1") (pin "2") (pinfunction "2_2") (pintype "passive"))
    )
    (net (code "59") (name "VCC_5V") (class "Default")
      (node (ref "3.3V_LDO") (pin "3") (pinfunction "VIN_3") (pintype "passive"))
      (node (ref "C15") (pin "1") (pinfunction "1_1") (pintype "passive"))
      (node (ref "C16") (pin "1") (pinfunction "1_1") (pintype "passive"))
      (node (ref "C5") (pin "1") (pinfunction "1_1") (pintype "passive"))
      (node (ref "C6") (pin "1") (pinfunction "1_1") (pintype "passive"))
      (node (ref "P5V") (pin "1") (pinfunction "1_1") (pintype "passive"))
      (node (ref "PCM_24bit") (pin "5V") (pinfunction "5V_5V") (pintype "passive"))
      (node (ref "PVin") (pin "1") (pinfunction "1_1") (pintype "passive"))
      (node (ref "R_M2") (pin "2") (pinfunction "2_2") (pintype "passive"))
    )
    (net (code "60") (name "VCC_12V") (class "Default")
      (node (ref "LM2596") (pin "Vin+") (pinfunction "Vin+_Vin+") (pintype "passive"))
      (node (ref "PVin") (pin "3") (pinfunction "3_3") (pintype "passive"))
    )
    (net (code "61") (name "VIN") (class "Default")
      (node (ref "PVin") (pin "2") (pinfunction "2_2") (pintype "passive"))
      (node (ref "Vin") (pin "2") (pinfunction "2_2") (pintype "passive"))
    )
    (net (code "62") (name "unconnected-(BOOT-NO_1-Pad3)") (class "Default")
      (node (ref "BOOT") (pin "3") (pinfunction "NO_1_3") (pintype "passive"))
    )
    (net (code "63") (name "unconnected-(BOOT-NO_2-Pad4)") (class "Default")
      (node (ref "BOOT") (pin "4") (pinfunction "NO_2_4") (pintype "passive"))
    )
    (net (code "64") (name "unconnected-(MicroSD_Card-Detech-Pad3)") (class "Default")
      (node (ref "MicroSD_Card") (pin "3") (pinfunction "Detech_3") (pintype "passive"))
    )
    (net (code "65") (name "unconnected-(MicroSD_Card-NC-Pad9)") (class "Default")
      (node (ref "MicroSD_Card") (pin "9") (pinfunction "NC_9") (pintype "passive"))
    )
    (net (code "66") (name "unconnected-(MicroSD_Card-NC{slash}nIRQ-Pad8)") (class "Default")
      (node (ref "MicroSD_Card") (pin "8") (pinfunction "NC/nIRQ_8") (pintype "passive"))
    )
    (net (code "67") (name "unconnected-(RST-NO_1-Pad3)") (class "Default")
      (node (ref "RST") (pin "3") (pinfunction "NO_1_3") (pintype "passive"))
    )
    (net (code "68") (name "unconnected-(RST-NO_2-Pad4)") (class "Default")
      (node (ref "RST") (pin "4") (pinfunction "NO_2_4") (pintype "passive"))
    )
    (net (code "69") (name "unconnected-(RTC_Module-Pad32K)") (class "Default")
      (node (ref "RTC_Module") (pin "32K") (pinfunction "32K_32K") (pintype "passive"))
    )
    (net (code "70") (name "unconnected-(RTC_Module-PadGND_1)") (class "Default")
      (node (ref "RTC_Module") (pin "GND_1") (pinfunction "GND_1_GND_1") (pintype "passive"))
    )
    (net (code "71") (name "unconnected-(RTC_Module-PadSCL_1)") (class "Default")
      (node (ref "RTC_Module") (pin "SCL_1") (pinfunction "SCL_1_SCL_1") (pintype "passive"))
    )
    (net (code "72") (name "unconnected-(RTC_Module-PadSDA_1)") (class "Default")
      (node (ref "RTC_Module") (pin "SDA_1") (pinfunction "SDA_1_SDA_1") (pintype "passive"))
    )
    (net (code "73") (name "unconnected-(RTC_Module-PadSQW)") (class "Default")
      (node (ref "RTC_Module") (pin "SQW") (pinfunction "SQW_SQW") (pintype "passive"))
    )
    (net (code "74") (name "unconnected-(RTC_Module-PadVCC_1)") (class "Default")
      (node (ref "RTC_Module") (pin "VCC_1") (pinfunction "VCC_1_VCC_1") (pintype "passive"))
    )
  )
)
